# myStravaB_V2.net
KiCad netlist of a schematic drawn in EAGLE
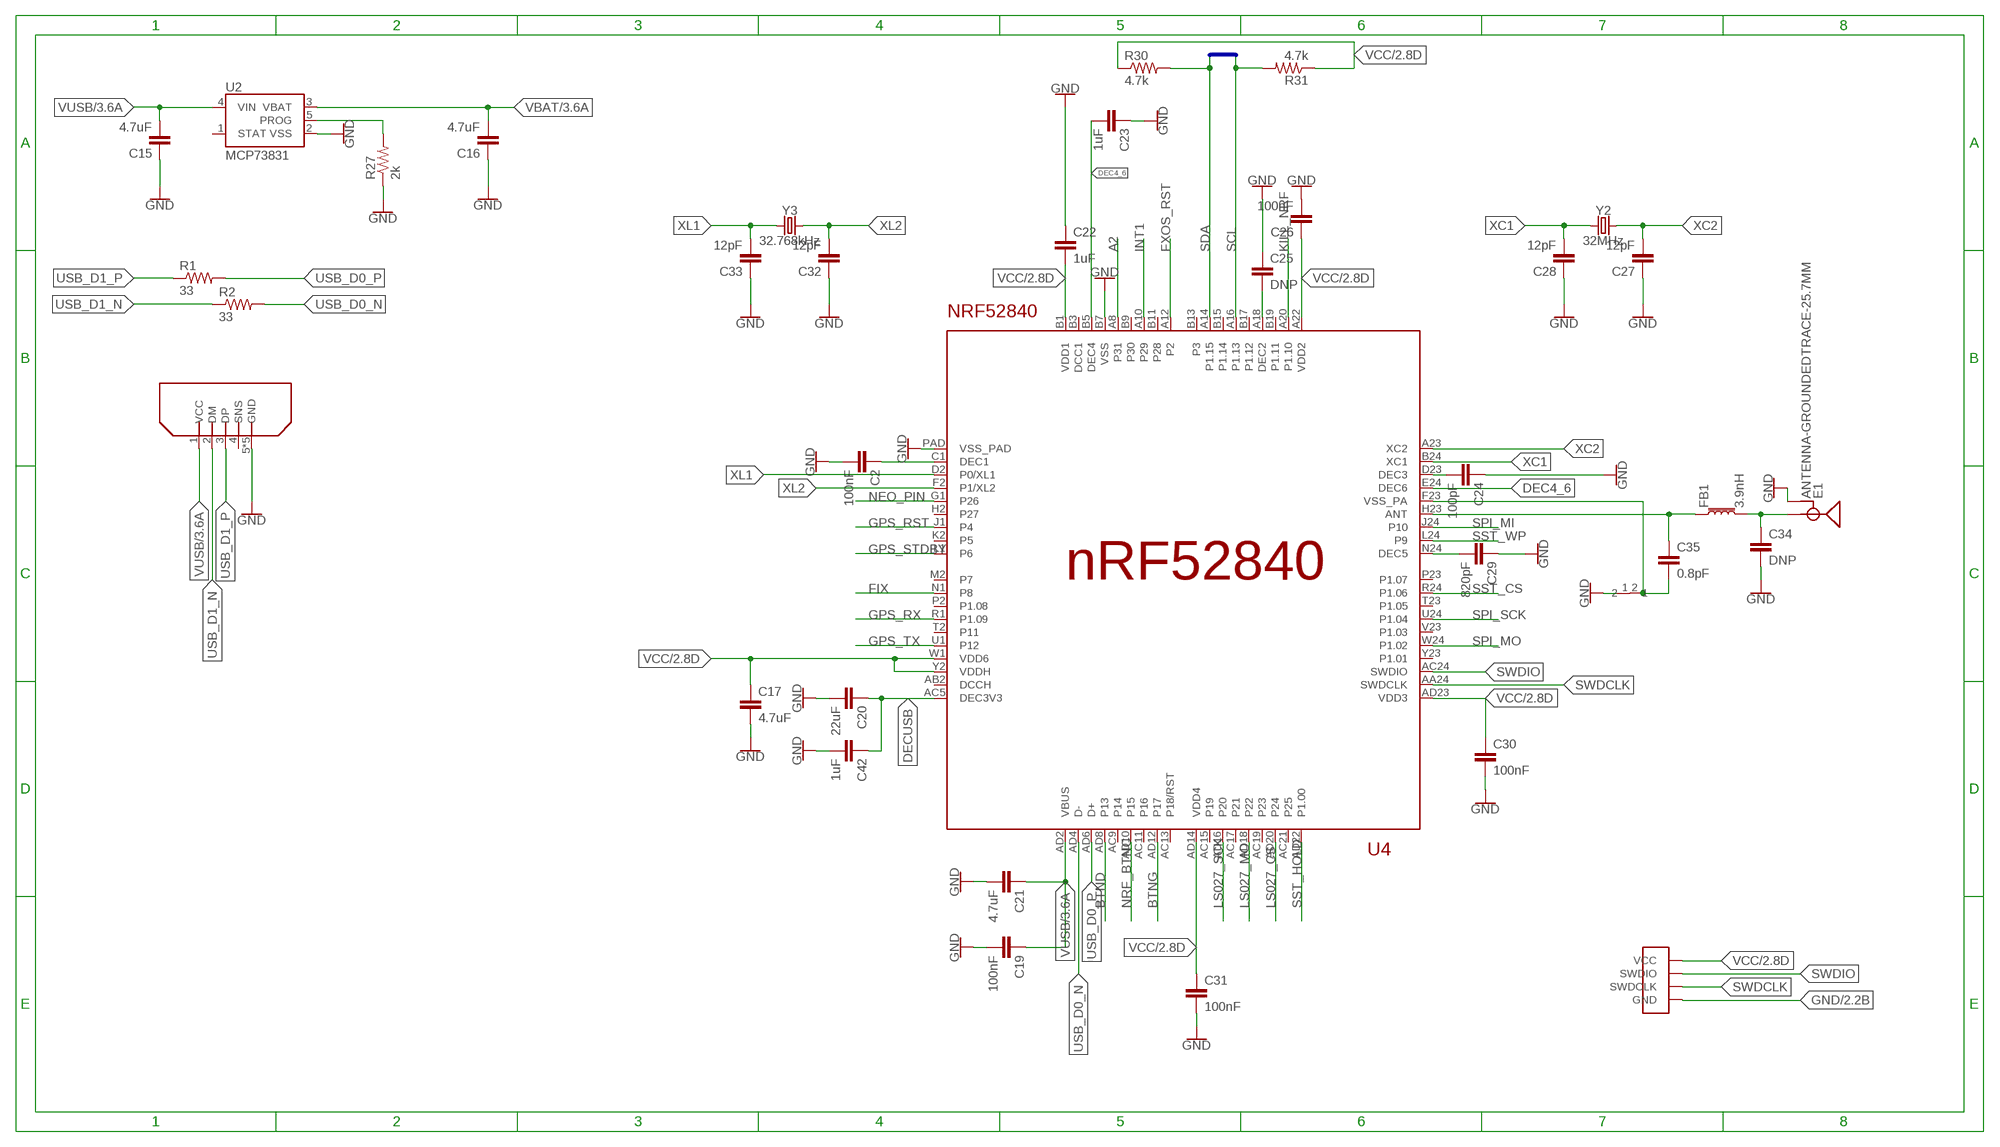
[diagram p0: schematic, sheet 1]
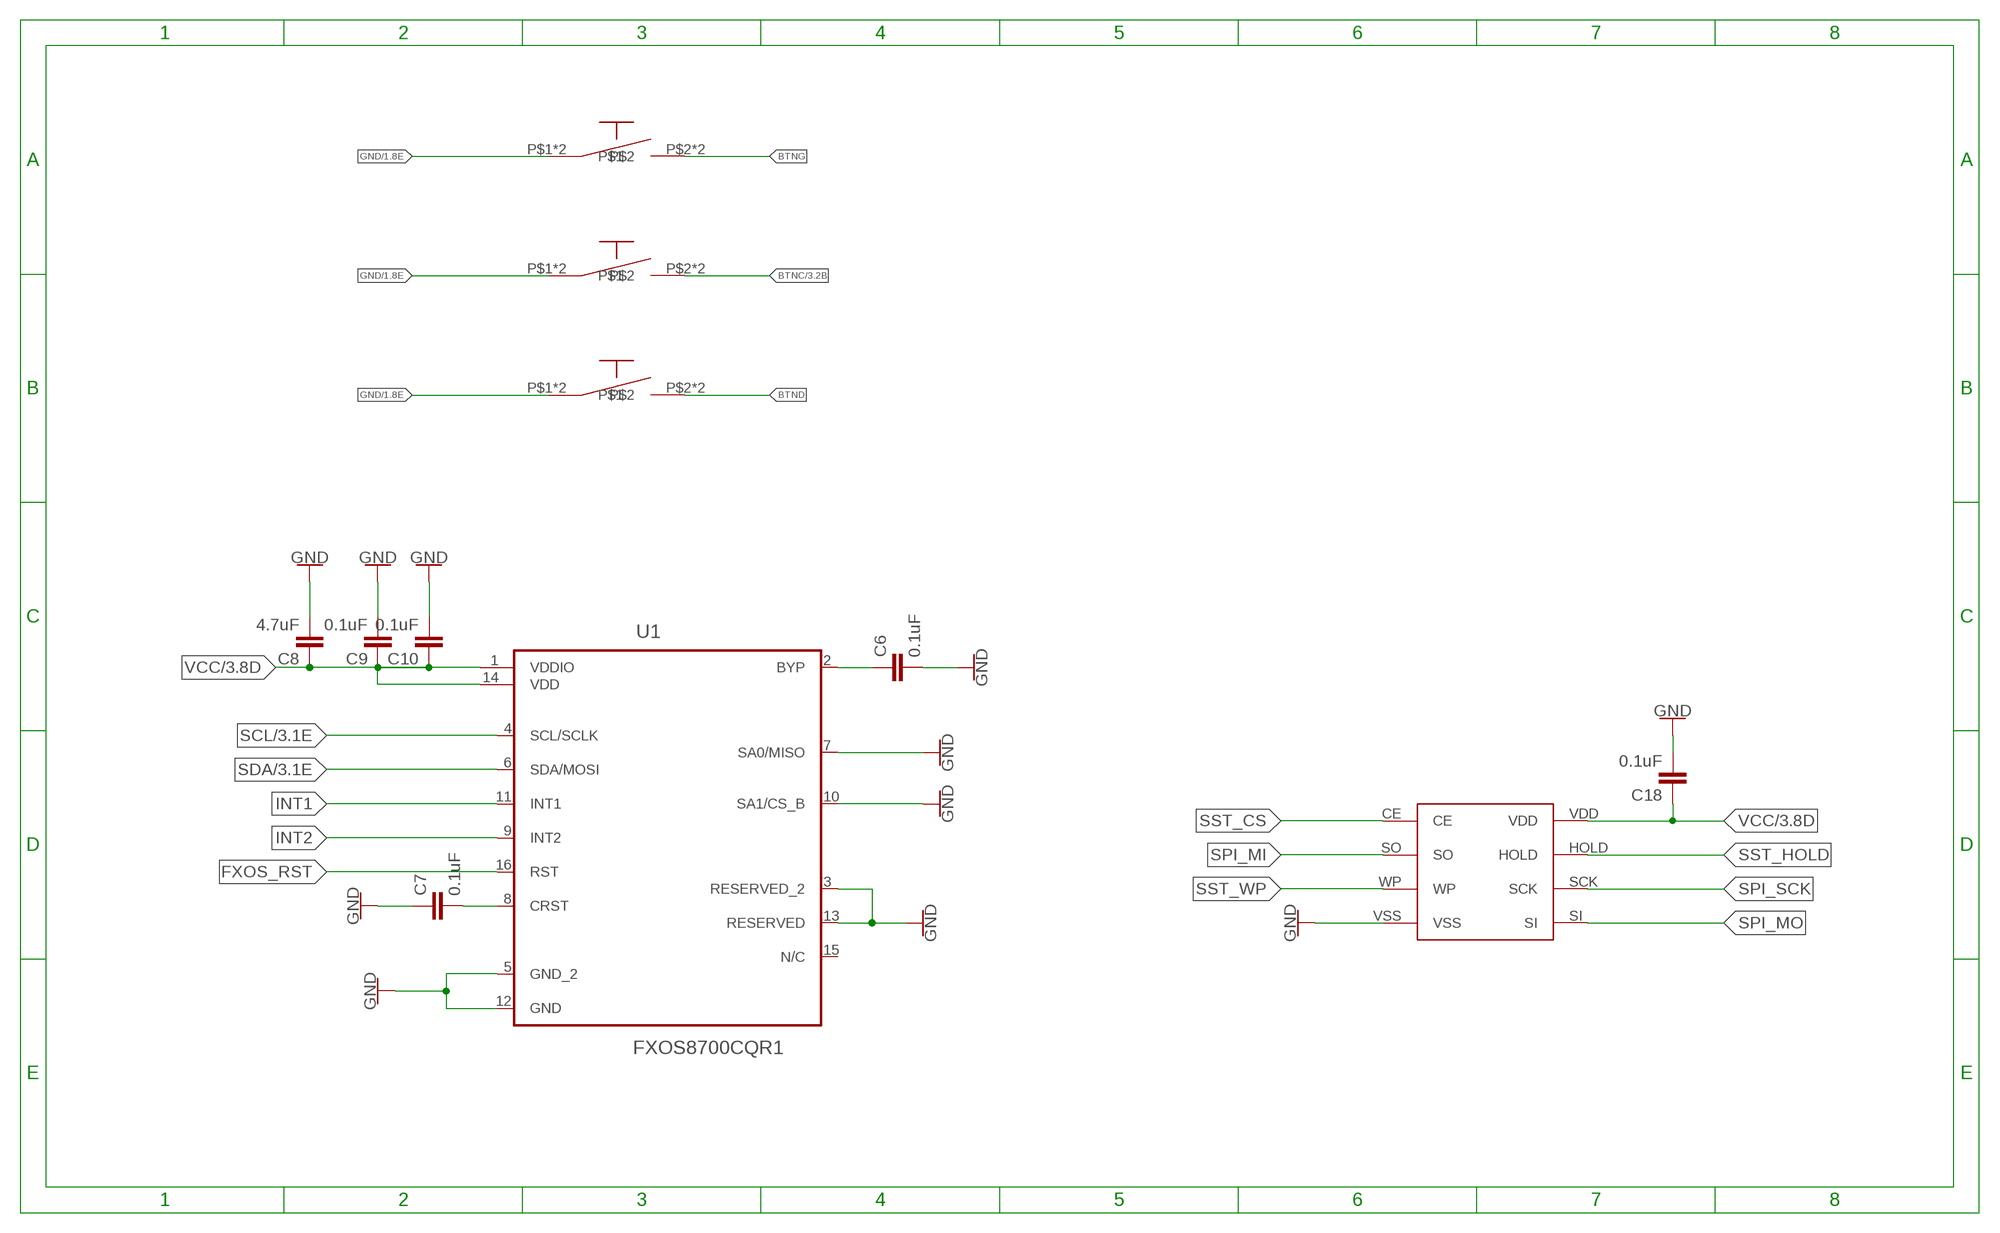
[diagram p1: schematic, sheet 2]
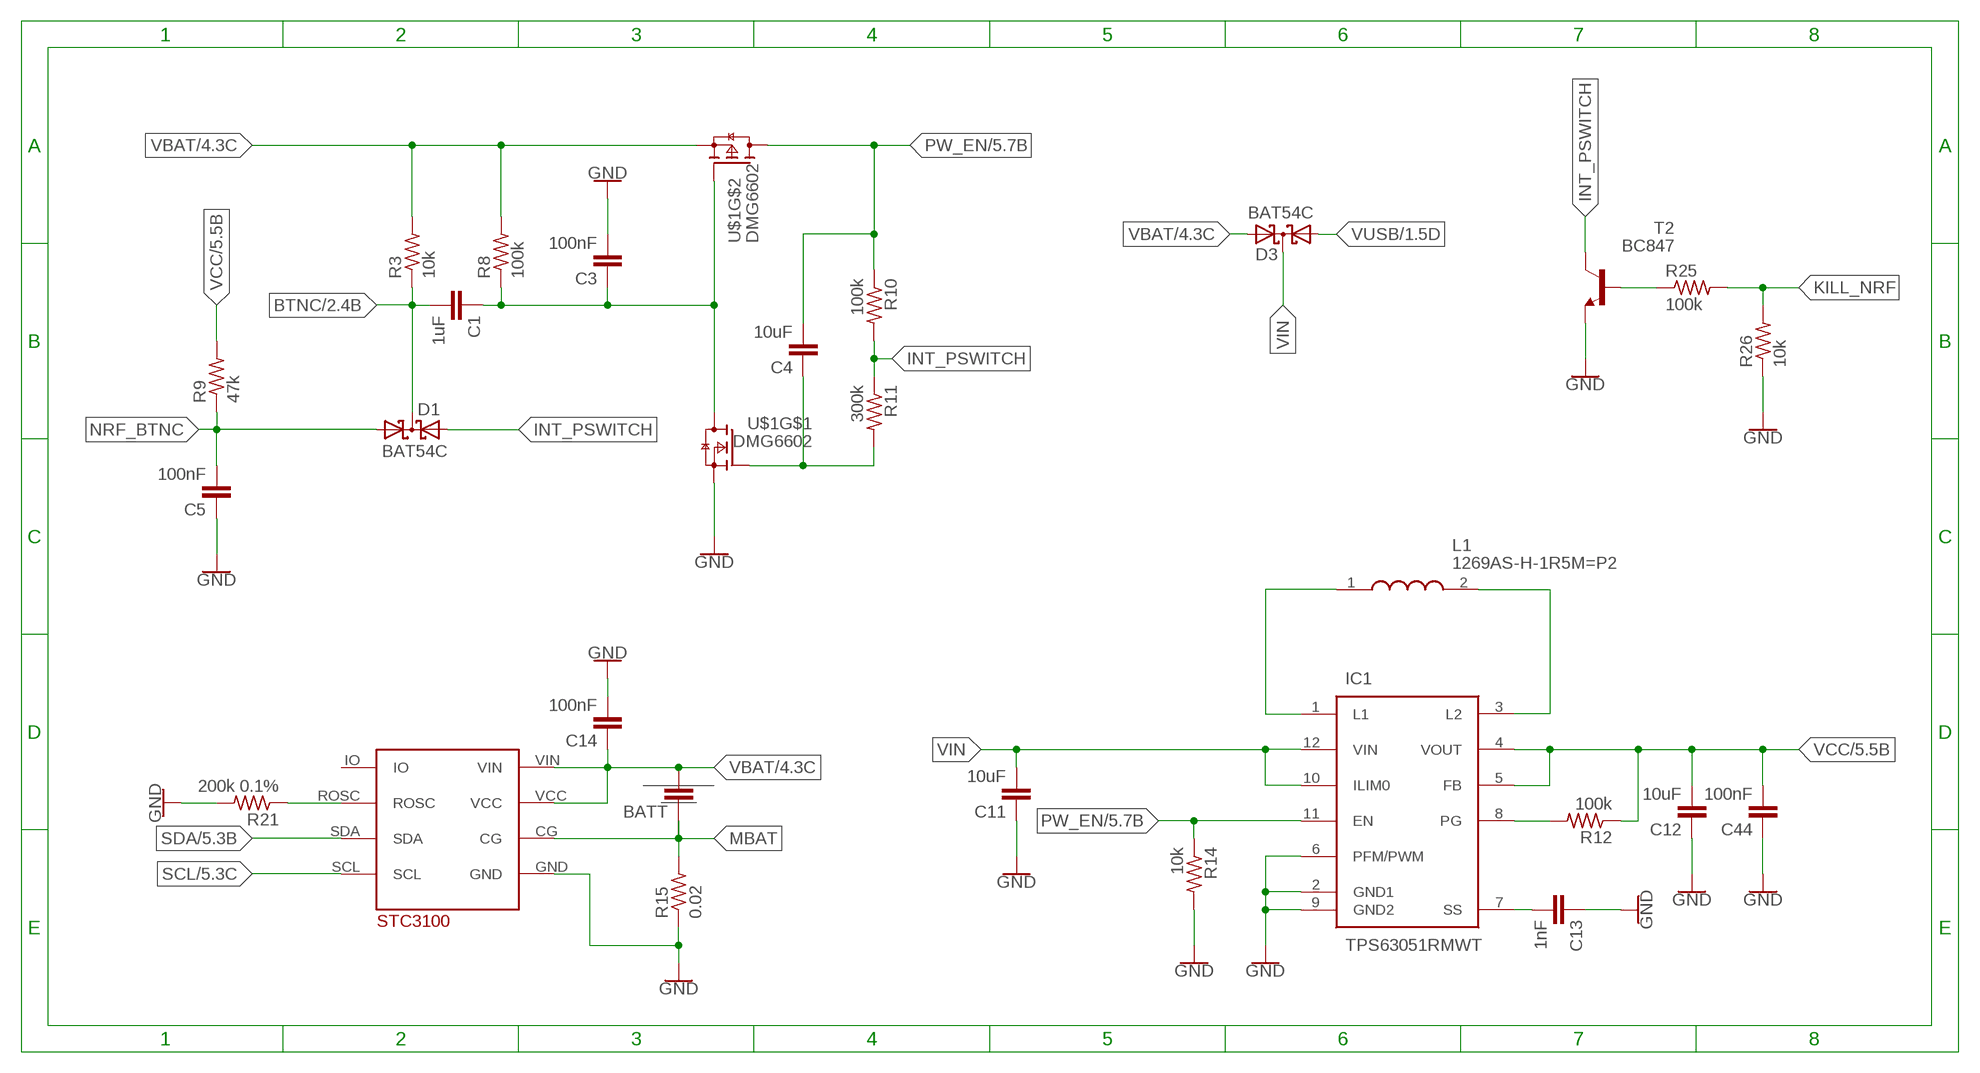
[diagram p2: schematic, sheet 3]
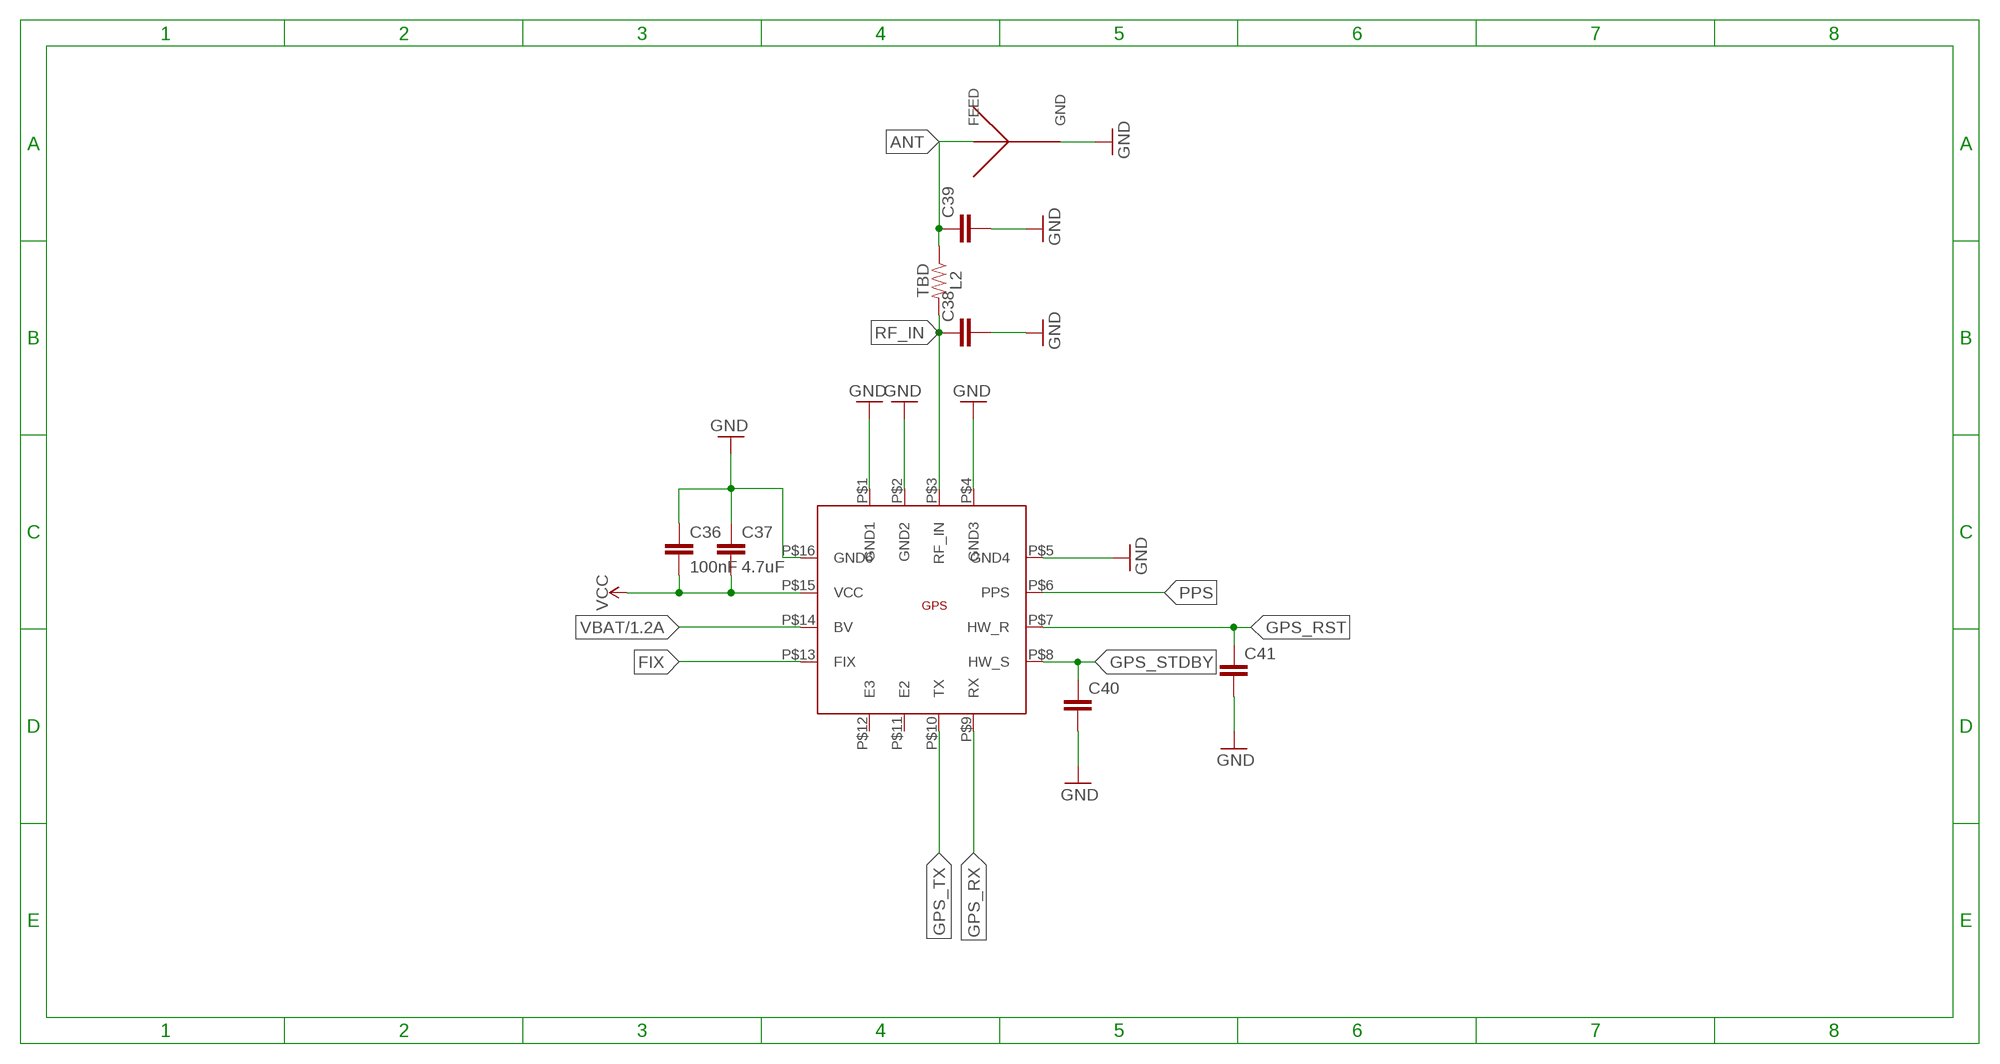
[diagram p3: schematic, sheet 4]
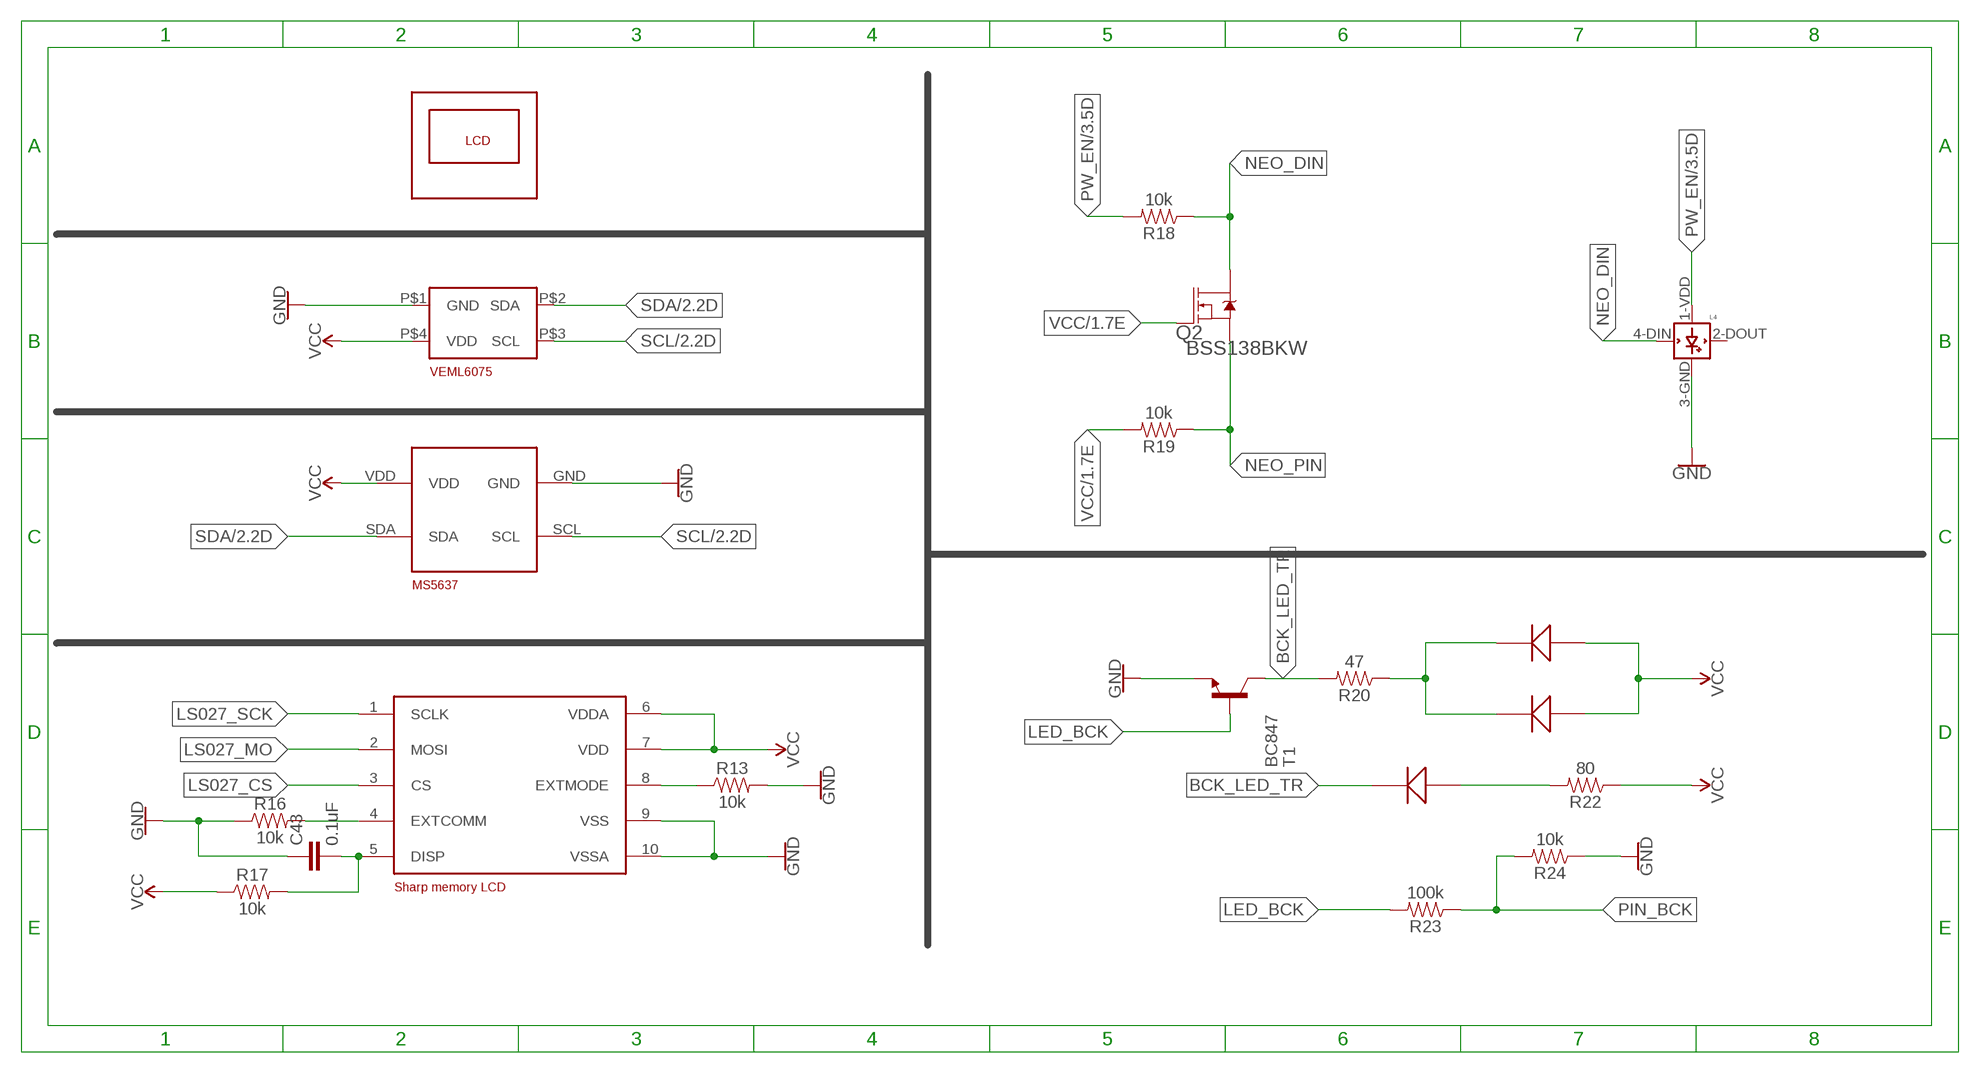
[diagram p4: schematic, sheet 5]

(export (version "E")
  (design (tool "Eeschema 10.0.6"))
  (components
    (comp (ref "C43")
      (value "0.1uF")
      (footprint "eagle-import:0603")
      (libsource (lib "eagle-import") (part "0.1UF-0603-25V-(+80/-20%)"))
    )
    (comp (ref "L4")
      (value "WS2812B")
      (footprint "eagle-import:WS2812B")
      (libsource (lib "eagle-import") (part "WS2812B"))
    )
    (comp (ref "MS1")
      (value "MS5637")
      (footprint "eagle-import:MS5637")
      (libsource (lib "eagle-import") (part "MS5637"))
    )
    (comp (ref "Q2")
      (value "BSS138BKW")
      (footprint "eagle-import:SOT65P210X110-3N")
      (libsource (lib "eagle-import") (part "BSS138BKW"))
    )
    (comp (ref "R13")
      (value "10k")
      (footprint "eagle-import:0603")
      (libsource (lib "eagle-import") (part "4.7KOHM-0603-1/10W-1%"))
    )
    (comp (ref "R16")
      (value "10k")
      (footprint "eagle-import:0603")
      (libsource (lib "eagle-import") (part "4.7KOHM-0603-1/10W-1%"))
    )
    (comp (ref "R17")
      (value "10k")
      (footprint "eagle-import:0603")
      (libsource (lib "eagle-import") (part "4.7KOHM-0603-1/10W-1%"))
    )
    (comp (ref "R18")
      (value "10k")
      (footprint "eagle-import:0603")
      (libsource (lib "eagle-import") (part "4.7KOHM-0603-1/10W-1%"))
    )
    (comp (ref "R19")
      (value "10k")
      (footprint "eagle-import:0603")
      (libsource (lib "eagle-import") (part "4.7KOHM-0603-1/10W-1%"))
    )
    (comp (ref "R20")
      (value "47")
      (footprint "eagle-import:0603")
      (libsource (lib "eagle-import") (part "4.7KOHM-0603-1/10W-1%"))
    )
    (comp (ref "R22")
      (value "80")
      (footprint "eagle-import:0603")
      (libsource (lib "eagle-import") (part "4.7KOHM-0603-1/10W-1%"))
    )
    (comp (ref "R23")
      (value "100k")
      (footprint "eagle-import:0603")
      (libsource (lib "eagle-import") (part "4.7KOHM-0603-1/10W-1%"))
    )
    (comp (ref "R24")
      (value "10k")
      (footprint "eagle-import:0603")
      (libsource (lib "eagle-import") (part "4.7KOHM-0603-1/10W-1%"))
    )
    (comp (ref "T1")
      (value "BC847")
      (footprint "eagle-import:SOT23")
      (libsource (lib "eagle-import") (part "BC847"))
    )
    (comp (ref "U$14")
      (value "VEML6075")
      (footprint "eagle-import:VEML6075")
      (libsource (lib "eagle-import") (part "VEML6075"))
    )
    (comp (ref "U$15")
      (value "SHARP27_FOOTPRINT")
      (footprint "eagle-import:LCD27")
      (libsource (lib "eagle-import") (part "SHARP27_FOOTPRINT"))
    )
    (comp (ref "U$16")
      (value "SHARP27")
      (footprint "eagle-import:SHARP27")
      (libsource (lib "eagle-import") (part "SHARP27"))
    )
    (comp (ref "U$17")
      (value "KPA-2106SECK")
      (footprint "eagle-import:KPA-2106SECK")
      (libsource (lib "eagle-import") (part "KPA-2106SECK"))
    )
    (comp (ref "U$18")
      (value "KPA-2106SECK")
      (footprint "eagle-import:KPA-2106SECK")
      (libsource (lib "eagle-import") (part "KPA-2106SECK"))
    )
    (comp (ref "U$19")
      (value "KPA-2106SECK")
      (footprint "eagle-import:KPA-2106SECK")
      (libsource (lib "eagle-import") (part "KPA-2106SECK"))
    )
    (comp (ref "C36")
      (value "100nF")
      (footprint "eagle-import:C0603")
      (libsource (lib "eagle-import") (part "rcl_334_C-EUC0603"))
    )
    (comp (ref "C37")
      (value "4.7uF")
      (footprint "eagle-import:C0603")
      (libsource (lib "eagle-import") (part "rcl_334_C-EUC0603"))
    )
    (comp (ref "C38")
      (value "C-EUC0603")
      (footprint "eagle-import:C0603")
      (libsource (lib "eagle-import") (part "rcl_334_C-EUC0603"))
    )
    (comp (ref "C39")
      (value "C-EUC0603")
      (footprint "eagle-import:C0603")
      (libsource (lib "eagle-import") (part "rcl_334_C-EUC0603"))
    )
    (comp (ref "C40")
      (value "C-EUC0603")
      (footprint "eagle-import:C0603")
      (libsource (lib "eagle-import") (part "rcl_334_C-EUC0603"))
    )
    (comp (ref "C41")
      (value "C-EUC0603")
      (footprint "eagle-import:C0603")
      (libsource (lib "eagle-import") (part "rcl_334_C-EUC0603"))
    )
    (comp (ref "L2")
      (value "TBD")
      (footprint "eagle-import:0603")
      (libsource (lib "eagle-import") (part "4.7KOHM-0603-1/10W-1%"))
    )
    (comp (ref "U$4")
      (value "SR4G008")
      (footprint "eagle-import:SR4G008")
      (libsource (lib "eagle-import") (part "SR4G008"))
    )
    (comp (ref "U$5")
      (value "M10578")
      (footprint "eagle-import:M10578")
      (libsource (lib "eagle-import") (part "M10578"))
    )
    (comp (ref "C2")
      (value "100nF")
      (footprint "eagle-import:C0603")
      (libsource (lib "eagle-import") (part "C-EUC0603"))
    )
    (comp (ref "C15")
      (value "4.7uF")
      (footprint "eagle-import:C0805")
      (libsource (lib "eagle-import") (part "C-EUC0805"))
    )
    (comp (ref "C16")
      (value "4.7uF")
      (footprint "eagle-import:C0805")
      (libsource (lib "eagle-import") (part "C-EUC0805"))
    )
    (comp (ref "C17")
      (value "4.7uF")
      (footprint "eagle-import:C0603")
      (libsource (lib "eagle-import") (part "rcl_334_C-EUC0603"))
    )
    (comp (ref "C19")
      (value "100nF")
      (footprint "eagle-import:C0603")
      (libsource (lib "eagle-import") (part "rcl_334_C-EUC0603"))
    )
    (comp (ref "C20")
      (value "22uF")
      (footprint "eagle-import:C0603")
      (libsource (lib "eagle-import") (part "rcl_334_C-EUC0603"))
    )
    (comp (ref "C21")
      (value "4.7uF")
      (footprint "eagle-import:C0805")
      (libsource (lib "eagle-import") (part "rcl_334_C-EUC0805"))
    )
    (comp (ref "C22")
      (value "1uF")
      (footprint "eagle-import:0603")
      (libsource (lib "eagle-import") (part "4.7UF0603"))
    )
    (comp (ref "C23")
      (value "1uF")
      (footprint "eagle-import:0603")
      (libsource (lib "eagle-import") (part "4.7UF0603"))
    )
    (comp (ref "C24")
      (value "100pF")
      (footprint "eagle-import:C0603")
      (libsource (lib "eagle-import") (part "C-EUC0603"))
    )
    (comp (ref "C25")
      (value "DNP")
      (footprint "eagle-import:C0402")
      (libsource (lib "eagle-import") (part "C-EUC0402"))
    )
    (comp (ref "C26")
      (value "100nF")
      (footprint "eagle-import:C0603")
      (libsource (lib "eagle-import") (part "C-EUC0603"))
    )
    (comp (ref "C27")
      (value "12pF")
      (footprint "eagle-import:C0402")
      (libsource (lib "eagle-import") (part "C-EUC0402"))
    )
    (comp (ref "C28")
      (value "12pF")
      (footprint "eagle-import:C0402")
      (libsource (lib "eagle-import") (part "C-EUC0402"))
    )
    (comp (ref "C29")
      (value "820pF")
      (footprint "eagle-import:C0603")
      (libsource (lib "eagle-import") (part "C-EUC0603"))
    )
    (comp (ref "C30")
      (value "100nF")
      (footprint "eagle-import:C0402")
      (libsource (lib "eagle-import") (part "C-EUC0402"))
    )
    (comp (ref "C31")
      (value "100nF")
      (footprint "eagle-import:C0402")
      (libsource (lib "eagle-import") (part "C-EUC0402"))
    )
    (comp (ref "C32")
      (value "12pF")
      (footprint "eagle-import:C0603")
      (libsource (lib "eagle-import") (part "C-EUC0603"))
    )
    (comp (ref "C33")
      (value "12pF")
      (footprint "eagle-import:C0603")
      (libsource (lib "eagle-import") (part "C-EUC0603"))
    )
    (comp (ref "C34")
      (value "DNP")
      (footprint "eagle-import:0603")
      (libsource (lib "eagle-import") (part "4.7UF0603"))
    )
    (comp (ref "C35")
      (value "0.8pF")
      (footprint "eagle-import:C0402")
      (libsource (lib "eagle-import") (part "C-EUC0402"))
    )
    (comp (ref "C42")
      (value "1uF")
      (footprint "eagle-import:C0603")
      (libsource (lib "eagle-import") (part "rcl_334_C-EUC0603"))
    )
    (comp (ref "E1")
      (value "ANTENNA-GROUNDEDTRACE-25.7MM")
      (footprint "eagle-import:TRACE_ANTENNA_2.4GHZ_25.7MM")
      (libsource (lib "eagle-import") (part "ANTENNA-GROUNDEDTRACE-25.7MM"))
    )
    (comp (ref "FB1")
      (value "3.9nH")
      (footprint "eagle-import:0603")
      (libsource (lib "eagle-import") (part "FERRITE_BEAD-0603"))
    )
    (comp (ref "R1")
      (value "33")
      (footprint "eagle-import:R0603")
      (libsource (lib "eagle-import") (part "R-US_R0603"))
    )
    (comp (ref "R2")
      (value "33")
      (footprint "eagle-import:R0603")
      (libsource (lib "eagle-import") (part "R-US_R0603"))
    )
    (comp (ref "R27")
      (value "2k")
      (footprint "eagle-import:R0603")
      (libsource (lib "eagle-import") (part "R-US_R0603"))
    )
    (comp (ref "R30")
      (value "4.7k")
      (footprint "eagle-import:R0603")
      (libsource (lib "eagle-import") (part "R-US_R0603"))
    )
    (comp (ref "R31")
      (value "4.7k")
      (footprint "eagle-import:R0603")
      (libsource (lib "eagle-import") (part "R-US_R0603"))
    )
    (comp (ref "U$3")
      (value "ZX80B5P")
      (footprint "eagle-import:ZX80B5P")
      (libsource (lib "eagle-import") (part "ZX80B5P"))
    )
    (comp (ref "U$7")
      (value "PROG_SMD")
      (footprint "eagle-import:PROG_SMD")
      (libsource (lib "eagle-import") (part "PROG_SMD"))
    )
    (comp (ref "U$8")
      (value "NET_CONN")
      (footprint "eagle-import:NET_CONN")
      (libsource (lib "eagle-import") (part "NET_CONN"))
    )
    (comp (ref "U2")
      (value "MCP73831")
      (footprint "eagle-import:SOT23-5")
      (libsource (lib "eagle-import") (part "MCP73831"))
    )
    (comp (ref "U4")
      (value "NRF52840")
      (footprint "eagle-import:AQFN73")
      (fields (field (name "SPICEPREFIX") "X"))
      (libsource (lib "eagle-import") (part "NRF52840"))
    )
    (comp (ref "Y2")
      (value "32MHz")
      (footprint "eagle-import:CRYSTAL-SMD-5X3.2-4PAD")
      (libsource (lib "eagle-import") (part "CRYSTAL-16MHZSMD-5X3.2"))
    )
    (comp (ref "Y3")
      (value "32.768kHz")
      (footprint "eagle-import:CRYSTAL-SMD-3.2X1.5MM")
      (libsource (lib "eagle-import") (part "CRYSTAL-32.768KHZSMD-3.2X1.5"))
    )
    (comp (ref "BATT")
      (value "C-EUC1210")
      (footprint "eagle-import:C1210")
      (libsource (lib "eagle-import") (part "rcl_334_C-EUC1210"))
    )
    (comp (ref "C1")
      (value "1uF")
      (footprint "eagle-import:0603")
      (libsource (lib "eagle-import") (part "4.7UF0603"))
    )
    (comp (ref "C3")
      (value "100nF")
      (footprint "eagle-import:0603")
      (libsource (lib "eagle-import") (part "4.7UF0603"))
    )
    (comp (ref "C4")
      (value "10uF")
      (footprint "eagle-import:0603")
      (libsource (lib "eagle-import") (part "4.7UF0603"))
    )
    (comp (ref "C5")
      (value "100nF")
      (footprint "eagle-import:0603")
      (libsource (lib "eagle-import") (part "4.7UF0603"))
    )
    (comp (ref "C11")
      (value "10uF")
      (footprint "eagle-import:C0805")
      (libsource (lib "eagle-import") (part "rcl_334_C-EUC0805"))
    )
    (comp (ref "C12")
      (value "10uF")
      (footprint "eagle-import:C0603")
      (libsource (lib "eagle-import") (part "rcl_334_C-EUC0603"))
    )
    (comp (ref "C13")
      (value "1nF")
      (footprint "eagle-import:C0603")
      (libsource (lib "eagle-import") (part "rcl_334_C-EUC0603"))
    )
    (comp (ref "C14")
      (value "100nF")
      (footprint "eagle-import:C0603")
      (libsource (lib "eagle-import") (part "rcl_334_C-EUC0603"))
    )
    (comp (ref "C44")
      (value "100nF")
      (footprint "eagle-import:C0603")
      (libsource (lib "eagle-import") (part "rcl_334_C-EUC0603"))
    )
    (comp (ref "D1")
      (value "BAT54C")
      (footprint "eagle-import:SOT23")
      (libsource (lib "eagle-import") (part "BAT54C"))
    )
    (comp (ref "D3")
      (value "BAT54C")
      (footprint "eagle-import:SOT23")
      (libsource (lib "eagle-import") (part "BAT54C"))
    )
    (comp (ref "IC1")
      (value "TPS63051RMWT")
      (footprint "eagle-import:QFN50P250X250X100-12N")
      (fields (field (name "RS_PART_NUMBER") "1330763"))
      (libsource (lib "eagle-import") (part "TPS63051RMWT"))
    )
    (comp (ref "L1")
      (value "1269AS-H-1R5M=P2")
      (footprint "eagle-import:INDC2520X110N")
      (libsource (lib "eagle-import") (part "1269AS-H-1R5M=P2"))
    )
    (comp (ref "R3")
      (value "10k")
      (footprint "eagle-import:R0603")
      (libsource (lib "eagle-import") (part "R-US_R0603"))
    )
    (comp (ref "R8")
      (value "100k")
      (footprint "eagle-import:R0603")
      (libsource (lib "eagle-import") (part "R-US_R0603"))
    )
    (comp (ref "R9")
      (value "47k")
      (footprint "eagle-import:R0603")
      (libsource (lib "eagle-import") (part "R-US_R0603"))
    )
    (comp (ref "R10")
      (value "100k")
      (footprint "eagle-import:R0603")
      (libsource (lib "eagle-import") (part "R-US_R0603"))
    )
    (comp (ref "R11")
      (value "300k")
      (footprint "eagle-import:R0603")
      (libsource (lib "eagle-import") (part "R-US_R0603"))
    )
    (comp (ref "R12")
      (value "100k")
      (footprint "eagle-import:R0603")
      (libsource (lib "eagle-import") (part "R-US_R0603"))
    )
    (comp (ref "R14")
      (value "10k")
      (footprint "eagle-import:R0603")
      (libsource (lib "eagle-import") (part "R-US_R0603"))
    )
    (comp (ref "R15")
      (value "0.02")
      (footprint "eagle-import:R0603")
      (libsource (lib "eagle-import") (part "R-US_R0603"))
    )
    (comp (ref "R21")
      (value "200k 0.1%")
      (footprint "eagle-import:R0603")
      (libsource (lib "eagle-import") (part "R-US_R0603"))
    )
    (comp (ref "R25")
      (value "100k")
      (footprint "eagle-import:R0603")
      (libsource (lib "eagle-import") (part "R-US_R0603"))
    )
    (comp (ref "R26")
      (value "10k")
      (footprint "eagle-import:R0603")
      (libsource (lib "eagle-import") (part "R-US_R0603"))
    )
    (comp (ref "T2")
      (value "BC847")
      (footprint "eagle-import:SOT23")
      (libsource (lib "eagle-import") (part "BC847"))
    )
    (comp (ref "U$1")
      (value "DMG6602")
      (footprint "eagle-import:TSOT26")
      (fields (field (name "MPN") "DMG6602SVTQ"))
      (libsource (lib "eagle-import") (part "DMG6602"))
    )
    (comp (ref "U$6")
      (value "STC3100")
      (footprint "eagle-import:STC3100")
      (libsource (lib "eagle-import") (part "STC3100"))
    )
    (comp (ref "BTNC1")
      (value "SKRMAAE010")
      (footprint "eagle-import:SKRMAAE010")
      (libsource (lib "eagle-import") (part "SKRMAAE010"))
    )
    (comp (ref "BTND1")
      (value "SKRMAAE010")
      (footprint "eagle-import:SKRMAAE010")
      (libsource (lib "eagle-import") (part "SKRMAAE010"))
    )
    (comp (ref "BTNG1")
      (value "SKRMAAE010")
      (footprint "eagle-import:SKRMAAE010")
      (libsource (lib "eagle-import") (part "SKRMAAE010"))
    )
    (comp (ref "C6")
      (value "0.1uF")
      (footprint "eagle-import:0603")
      (libsource (lib "eagle-import") (part "4.7UF0603"))
    )
    (comp (ref "C7")
      (value "0.1uF")
      (footprint "eagle-import:0603")
      (libsource (lib "eagle-import") (part "4.7UF0603"))
    )
    (comp (ref "C8")
      (value "4.7uF")
      (footprint "eagle-import:0603")
      (libsource (lib "eagle-import") (part "4.7UF0603"))
    )
    (comp (ref "C9")
      (value "0.1uF")
      (footprint "eagle-import:0603")
      (libsource (lib "eagle-import") (part "4.7UF0603"))
    )
    (comp (ref "C10")
      (value "0.1uF")
      (footprint "eagle-import:0603")
      (libsource (lib "eagle-import") (part "4.7UF0603"))
    )
    (comp (ref "C18")
      (value "0.1uF")
      (footprint "eagle-import:0603")
      (libsource (lib "eagle-import") (part "4.7UF0603"))
    )
    (comp (ref "U$2")
      (value "FLASH")
      (footprint "eagle-import:SOIC8")
      (libsource (lib "eagle-import") (part "FLASH"))
    )
    (comp (ref "U1")
      (value "FXOS8700CQR1")
      (footprint "eagle-import:QFN50P300X300X120-16N")
      (libsource (lib "eagle-import") (part "FXOS8700CQR1"))
    )
  )
  (nets
    (net (code "1") (name "A2") (class "Default")
      (node (ref "U4") (pin "A8") (pinfunction "P31_A8") (pintype "bidirectional"))
    )
    (net (code "2") (name "ANT") (class "Default")
      (node (ref "C39") (pin "1") (pinfunction "1_1") (pintype "passive"))
      (node (ref "L2") (pin "1") (pinfunction "1_1") (pintype "passive"))
      (node (ref "U$4") (pin "P$2") (pinfunction "FEED_P$2") (pintype "bidirectional"))
    )
    (net (code "3") (name "BCK_LED_TR") (class "Default")
      (node (ref "R20") (pin "2") (pinfunction "2_2") (pintype "passive"))
      (node (ref "T1") (pin "3") (pinfunction "C_3") (pintype "passive"))
      (node (ref "U$19") (pin "P$1") (pinfunction "P$1_P$1") (pintype "bidirectional"))
    )
    (net (code "4") (name "BTNC") (class "Default")
      (node (ref "BTNC1") (pin "P$2") (pinfunction "P$2_P$2") (pintype "bidirectional"))
      (node (ref "BTNC1") (pin "P$4") (pinfunction "P$2_P$4") (pintype "bidirectional"))
      (node (ref "C1") (pin "2") (pinfunction "2_2") (pintype "passive"))
      (node (ref "D1") (pin "3") (pinfunction "CC_3") (pintype "passive"))
      (node (ref "R3") (pin "1") (pinfunction "1_1") (pintype "passive"))
    )
    (net (code "5") (name "BTND") (class "Default")
      (node (ref "BTND1") (pin "P$2") (pinfunction "P$2_P$2") (pintype "bidirectional"))
      (node (ref "BTND1") (pin "P$4") (pinfunction "P$2_P$4") (pintype "bidirectional"))
      (node (ref "U4") (pin "AD8") (pinfunction "P13_AD8") (pintype "bidirectional"))
    )
    (net (code "6") (name "BTNG") (class "Default")
      (node (ref "BTNG1") (pin "P$2") (pinfunction "P$2_P$2") (pintype "bidirectional"))
      (node (ref "BTNG1") (pin "P$4") (pinfunction "P$2_P$4") (pintype "bidirectional"))
      (node (ref "U4") (pin "AD12") (pinfunction "P17_AD12") (pintype "bidirectional"))
    )
    (net (code "7") (name "DEC4_6") (class "Default")
      (node (ref "C23") (pin "2") (pinfunction "2_2") (pintype "passive"))
      (node (ref "U4") (pin "B5") (pinfunction "DEC4_B5") (pintype "bidirectional"))
      (node (ref "U4") (pin "E24") (pinfunction "DEC6_E24") (pintype "bidirectional"))
    )
    (net (code "8") (name "DECUSB") (class "Default")
      (node (ref "C20") (pin "1") (pinfunction "1_1") (pintype "passive"))
      (node (ref "C42") (pin "1") (pinfunction "1_1") (pintype "passive"))
      (node (ref "U4") (pin "AC5") (pinfunction "DEC3V3_AC5") (pintype "bidirectional"))
    )
    (net (code "9") (name "FIX") (class "Default")
      (node (ref "U$5") (pin "P$13") (pinfunction "FIX_P$13") (pintype "bidirectional"))
      (node (ref "U4") (pin "N1") (pinfunction "P8_N1") (pintype "bidirectional"))
    )
    (net (code "10") (name "FXOS_RST") (class "Default")
      (node (ref "U1") (pin "16") (pinfunction "RST_16") (pintype "input"))
      (node (ref "U4") (pin "A12") (pinfunction "P2_A12") (pintype "bidirectional"))
    )
    (net (code "11") (name "GND") (class "Default")
      (node (ref "BTNC1") (pin "P$1") (pinfunction "P$1_P$1") (pintype "bidirectional"))
      (node (ref "BTNC1") (pin "P$3") (pinfunction "P$1_P$3") (pintype "bidirectional"))
      (node (ref "BTND1") (pin "P$1") (pinfunction "P$1_P$1") (pintype "bidirectional"))
      (node (ref "BTND1") (pin "P$3") (pinfunction "P$1_P$3") (pintype "bidirectional"))
      (node (ref "BTNG1") (pin "P$1") (pinfunction "P$1_P$1") (pintype "bidirectional"))
      (node (ref "BTNG1") (pin "P$3") (pinfunction "P$1_P$3") (pintype "bidirectional"))
      (node (ref "C10") (pin "2") (pinfunction "2_2") (pintype "passive"))
      (node (ref "C11") (pin "1") (pinfunction "1_1") (pintype "passive"))
      (node (ref "C12") (pin "1") (pinfunction "1_1") (pintype "passive"))
      (node (ref "C13") (pin "1") (pinfunction "1_1") (pintype "passive"))
      (node (ref "C14") (pin "2") (pinfunction "2_2") (pintype "passive"))
      (node (ref "C15") (pin "1") (pinfunction "1_1") (pintype "passive"))
      (node (ref "C16") (pin "1") (pinfunction "1_1") (pintype "passive"))
      (node (ref "C17") (pin "2") (pinfunction "2_2") (pintype "passive"))
      (node (ref "C18") (pin "2") (pinfunction "2_2") (pintype "passive"))
      (node (ref "C19") (pin "2") (pinfunction "2_2") (pintype "passive"))
      (node (ref "C2") (pin "2") (pinfunction "2_2") (pintype "passive"))
      (node (ref "C20") (pin "2") (pinfunction "2_2") (pintype "passive"))
      (node (ref "C21") (pin "2") (pinfunction "2_2") (pintype "passive"))
      (node (ref "C22") (pin "1") (pinfunction "1_1") (pintype "passive"))
      (node (ref "C23") (pin "1") (pinfunction "1_1") (pintype "passive"))
      (node (ref "C24") (pin "1") (pinfunction "1_1") (pintype "passive"))
      (node (ref "C25") (pin "1") (pinfunction "1_1") (pintype "passive"))
      (node (ref "C26") (pin "2") (pinfunction "2_2") (pintype "passive"))
      (node (ref "C27") (pin "1") (pinfunction "1_1") (pintype "passive"))
      (node (ref "C28") (pin "1") (pinfunction "1_1") (pintype "passive"))
      (node (ref "C29") (pin "1") (pinfunction "1_1") (pintype "passive"))
      (node (ref "C3") (pin "2") (pinfunction "2_2") (pintype "passive"))
      (node (ref "C30") (pin "2") (pinfunction "2_2") (pintype "passive"))
      (node (ref "C31") (pin "2") (pinfunction "2_2") (pintype "passive"))
      (node (ref "C32") (pin "1") (pinfunction "1_1") (pintype "passive"))
      (node (ref "C33") (pin "1") (pinfunction "1_1") (pintype "passive"))
      (node (ref "C34") (pin "2") (pinfunction "2_2") (pintype "passive"))
      (node (ref "C36") (pin "1") (pinfunction "1_1") (pintype "passive"))
      (node (ref "C37") (pin "1") (pinfunction "1_1") (pintype "passive"))
      (node (ref "C38") (pin "2") (pinfunction "2_2") (pintype "passive"))
      (node (ref "C39") (pin "2") (pinfunction "2_2") (pintype "passive"))
      (node (ref "C40") (pin "2") (pinfunction "2_2") (pintype "passive"))
      (node (ref "C41") (pin "2") (pinfunction "2_2") (pintype "passive"))
      (node (ref "C42") (pin "2") (pinfunction "2_2") (pintype "passive"))
      (node (ref "C43") (pin "1") (pinfunction "1_1") (pintype "passive"))
      (node (ref "C44") (pin "1") (pinfunction "1_1") (pintype "passive"))
      (node (ref "C5") (pin "1") (pinfunction "1_1") (pintype "passive"))
      (node (ref "C6") (pin "2") (pinfunction "2_2") (pintype "passive"))
      (node (ref "C7") (pin "1") (pinfunction "1_1") (pintype "passive"))
      (node (ref "C8") (pin "2") (pinfunction "2_2") (pintype "passive"))
      (node (ref "C9") (pin "2") (pinfunction "2_2") (pintype "passive"))
      (node (ref "E1") (pin "GND") (pinfunction "GND_GND") (pintype "bidirectional"))
      (node (ref "E1") (pin "GND2") (pinfunction "GND_GND2") (pintype "bidirectional"))
      (node (ref "IC1") (pin "2") (pinfunction "GND1_2") (pintype "bidirectional"))
      (node (ref "IC1") (pin "6") (pinfunction "PFM/PWM_6") (pintype "bidirectional"))
      (node (ref "IC1") (pin "9") (pinfunction "GND2_9") (pintype "bidirectional"))
      (node (ref "L4") (pin "3-GND") (pinfunction "GND_3-GND") (pintype "bidirectional"))
      (node (ref "MS1") (pin "GND") (pinfunction "GND_GND") (pintype "bidirectional"))
      (node (ref "R13") (pin "2") (pinfunction "2_2") (pintype "passive"))
      (node (ref "R14") (pin "2") (pinfunction "2_2") (pintype "passive"))
      (node (ref "R15") (pin "1") (pinfunction "1_1") (pintype "passive"))
      (node (ref "R16") (pin "1") (pinfunction "1_1") (pintype "passive"))
      (node (ref "R21") (pin "2") (pinfunction "2_2") (pintype "passive"))
      (node (ref "R24") (pin "1") (pinfunction "1_1") (pintype "passive"))
      (node (ref "R26") (pin "1") (pinfunction "1_1") (pintype "passive"))
      (node (ref "R27") (pin "1") (pinfunction "1_1") (pintype "passive"))
      (node (ref "T1") (pin "2") (pinfunction "E_2") (pintype "passive"))
      (node (ref "T2") (pin "2") (pinfunction "E_2") (pintype "passive"))
      (node (ref "U$1") (pin "P$5") (pinfunction "S_P$5") (pintype "passive"))
      (node (ref "U$14") (pin "P$1") (pinfunction "GND_P$1") (pintype "bidirectional"))
      (node (ref "U$16") (pin "10") (pinfunction "VSSA_10") (pintype "bidirectional"))
      (node (ref "U$16") (pin "9") (pinfunction "VSS_9") (pintype "bidirectional"))
      (node (ref "U$2") (pin "VSS") (pinfunction "VSS_VSS") (pintype "bidirectional"))
      (node (ref "U$3") (pin "5") (pinfunction "GND_5") (pintype "bidirectional"))
      (node (ref "U$3") (pin "GND1") (pinfunction "GND_GND1") (pintype "bidirectional"))
      (node (ref "U$3") (pin "GND2") (pinfunction "GND_GND2") (pintype "bidirectional"))
      (node (ref "U$3") (pin "GND3") (pinfunction "GND_GND3") (pintype "bidirectional"))
      (node (ref "U$3") (pin "GND4") (pinfunction "GND_GND4") (pintype "bidirectional"))
      (node (ref "U$4") (pin "P$3") (pinfunction "GND_P$3") (pintype "bidirectional"))
      (node (ref "U$4") (pin "P$4") (pinfunction "GND_P$4") (pintype "bidirectional"))
      (node (ref "U$4") (pin "P$6") (pinfunction "GND_P$6") (pintype "bidirectional"))
      (node (ref "U$5") (pin "P$1") (pinfunction "GND1_P$1") (pintype "bidirectional"))
      (node (ref "U$5") (pin "P$16") (pinfunction "GND6_P$16") (pintype "bidirectional"))
      (node (ref "U$5") (pin "P$2") (pinfunction "GND2_P$2") (pintype "bidirectional"))
      (node (ref "U$5") (pin "P$4") (pinfunction "GND3_P$4") (pintype "bidirectional"))
      (node (ref "U$5") (pin "P$5") (pinfunction "GND4_P$5") (pintype "bidirectional"))
      (node (ref "U$6") (pin "GND") (pinfunction "GND_GND") (pintype "bidirectional"))
      (node (ref "U$7") (pin "GND") (pinfunction "GND_GND") (pintype "bidirectional"))
      (node (ref "U$8") (pin "1") (pinfunction "1_1") (pintype "bidirectional"))
      (node (ref "U1") (pin "10") (pinfunction "SA1/CS_B_10") (pintype "input"))
      (node (ref "U1") (pin "12") (pinfunction "GND_12") (pintype "passive"))
      (node (ref "U1") (pin "13") (pinfunction "RESERVED_13") (pintype "passive"))
      (node (ref "U1") (pin "3") (pinfunction "RESERVED_2_3") (pintype "passive"))
      (node (ref "U1") (pin "5") (pinfunction "GND_2_5") (pintype "passive"))
      (node (ref "U1") (pin "7") (pinfunction "SA0/MISO_7") (pintype "bidirectional"))
      (node (ref "U2") (pin "2") (pinfunction "VSS_2") (pintype "power_in"))
      (node (ref "U4") (pin "B7") (pinfunction "VSS_B7") (pintype "bidirectional"))
      (node (ref "U4") (pin "PAD") (pinfunction "VSS_PAD_PAD") (pintype "bidirectional"))
    )
    (net (code "12") (name "GPS_RST") (class "Default")
      (node (ref "C41") (pin "1") (pinfunction "1_1") (pintype "passive"))
      (node (ref "U$5") (pin "P$7") (pinfunction "HW_R_P$7") (pintype "bidirectional"))
      (node (ref "U4") (pin "J1") (pinfunction "P4_J1") (pintype "bidirectional"))
    )
    (net (code "13") (name "GPS_RX") (class "Default")
      (node (ref "U$5") (pin "P$9") (pinfunction "RX_P$9") (pintype "bidirectional"))
      (node (ref "U4") (pin "R1") (pinfunction "P1.09_R1") (pintype "bidirectional"))
    )
    (net (code "14") (name "GPS_STDBY") (class "Default")
      (node (ref "C40") (pin "1") (pinfunction "1_1") (pintype "passive"))
      (node (ref "U$5") (pin "P$8") (pinfunction "HW_S_P$8") (pintype "bidirectional"))
      (node (ref "U4") (pin "L1") (pinfunction "P6_L1") (pintype "bidirectional"))
    )
    (net (code "15") (name "GPS_TX") (class "Default")
      (node (ref "U$5") (pin "P$10") (pinfunction "TX_P$10") (pintype "bidirectional"))
      (node (ref "U4") (pin "U1") (pinfunction "P12_U1") (pintype "bidirectional"))
    )
    (net (code "16") (name "INT1") (class "Default")
      (node (ref "U1") (pin "11") (pinfunction "INT1_11") (pintype "input"))
      (node (ref "U4") (pin "A10") (pinfunction "P29_A10") (pintype "bidirectional"))
    )
    (net (code "17") (name "INT2") (class "Default")
      (node (ref "U1") (pin "9") (pinfunction "INT2_9") (pintype "input"))
    )
    (net (code "18") (name "INT_PSWITCH") (class "Default")
      (node (ref "D1") (pin "2") (pinfunction "A2_2") (pintype "passive"))
      (node (ref "R10") (pin "2") (pinfunction "2_2") (pintype "passive"))
      (node (ref "R11") (pin "1") (pinfunction "1_1") (pintype "passive"))
      (node (ref "T2") (pin "3") (pinfunction "C_3") (pintype "passive"))
    )
    (net (code "19") (name "KILL_NRF") (class "Default")
      (node (ref "R25") (pin "2") (pinfunction "2_2") (pintype "passive"))
      (node (ref "R26") (pin "2") (pinfunction "2_2") (pintype "passive"))
      (node (ref "U4") (pin "A20") (pinfunction "P1.10_A20") (pintype "bidirectional"))
    )
    (net (code "20") (name "LED_BCK") (class "Default")
      (node (ref "R23") (pin "2") (pinfunction "2_2") (pintype "passive"))
      (node (ref "T1") (pin "1") (pinfunction "B_1") (pintype "passive"))
    )
    (net (code "21") (name "LS027_CS") (class "Default")
      (node (ref "U$16") (pin "3") (pinfunction "CS_3") (pintype "bidirectional"))
      (node (ref "U4") (pin "AD20") (pinfunction "P24_AD20") (pintype "bidirectional"))
    )
    (net (code "22") (name "LS027_MO") (class "Default")
      (node (ref "U$16") (pin "2") (pinfunction "MOSI_2") (pintype "bidirectional"))
      (node (ref "U4") (pin "AD18") (pinfunction "P22_AD18") (pintype "bidirectional"))
    )
    (net (code "23") (name "LS027_SCK") (class "Default")
      (node (ref "U$16") (pin "1") (pinfunction "SCLK_1") (pintype "bidirectional"))
      (node (ref "U4") (pin "AD16") (pinfunction "P20_AD16") (pintype "bidirectional"))
    )
    (net (code "24") (name "MBAT") (class "Default")
      (node (ref "BATT") (pin "1") (pinfunction "1_1") (pintype "passive"))
      (node (ref "R15") (pin "2") (pinfunction "2_2") (pintype "passive"))
      (node (ref "U$6") (pin "CG") (pinfunction "CG_CG") (pintype "bidirectional"))
    )
    (net (code "25") (name "NEO_DIN") (class "Default")
      (node (ref "L4") (pin "4-DIN") (pinfunction "DIN_4-DIN") (pintype "input"))
      (node (ref "Q2") (pin "3") (pinfunction "D_3") (pintype "bidirectional"))
      (node (ref "R18") (pin "1") (pinfunction "1_1") (pintype "passive"))
    )
    (net (code "26") (name "NEO_PIN") (class "Default")
      (node (ref "Q2") (pin "2") (pinfunction "S_2") (pintype "bidirectional"))
      (node (ref "R19") (pin "1") (pinfunction "1_1") (pintype "passive"))
      (node (ref "U4") (pin "G1") (pinfunction "P26_G1") (pintype "bidirectional"))
    )
    (net (code "27") (name "NRF_BTNC") (class "Default")
      (node (ref "C5") (pin "2") (pinfunction "2_2") (pintype "passive"))
      (node (ref "D1") (pin "1") (pinfunction "A1_1") (pintype "passive"))
      (node (ref "R9") (pin "1") (pinfunction "1_1") (pintype "passive"))
      (node (ref "U4") (pin "AD10") (pinfunction "P15_AD10") (pintype "bidirectional"))
    )
    (net (code "28") (name "Net-(E1-SIGNAL)") (class "Default")
      (node (ref "C34") (pin "1") (pinfunction "1_1") (pintype "passive"))
      (node (ref "E1") (pin "ANT") (pinfunction "SIGNAL_ANT") (pintype "bidirectional"))
      (node (ref "FB1") (pin "2") (pinfunction "2_2") (pintype "passive"))
    )
    (net (code "29") (name "Net-(IC1-L1)") (class "Default")
      (node (ref "IC1") (pin "1") (pinfunction "L1_1") (pintype "bidirectional"))
      (node (ref "L1") (pin "1") (pinfunction "1_1") (pintype "bidirectional"))
    )
    (net (code "30") (name "Net-(IC1-L2)") (class "Default")
      (node (ref "IC1") (pin "3") (pinfunction "L2_3") (pintype "bidirectional"))
      (node (ref "L1") (pin "2") (pinfunction "2_2") (pintype "bidirectional"))
    )
    (net (code "31") (name "Net-(IC1-PG)") (class "Default")
      (node (ref "IC1") (pin "8") (pinfunction "PG_8") (pintype "bidirectional"))
      (node (ref "R12") (pin "2") (pinfunction "2_2") (pintype "passive"))
    )
    (net (code "32") (name "Net-(IC1-SS)") (class "Default")
      (node (ref "C13") (pin "2") (pinfunction "2_2") (pintype "passive"))
      (node (ref "IC1") (pin "7") (pinfunction "SS_7") (pintype "bidirectional"))
    )
    (net (code "33") (name "Net-(R20-Pad1)") (class "Default")
      (node (ref "R20") (pin "1") (pinfunction "1_1") (pintype "passive"))
      (node (ref "U$17") (pin "P$1") (pinfunction "P$1_P$1") (pintype "bidirectional"))
      (node (ref "U$18") (pin "P$1") (pinfunction "P$1_P$1") (pintype "bidirectional"))
    )
    (net (code "34") (name "Net-(R21-Pad1)") (class "Default")
      (node (ref "R21") (pin "1") (pinfunction "1_1") (pintype "passive"))
      (node (ref "U$6") (pin "ROSC") (pinfunction "ROSC_ROSC") (pintype "bidirectional"))
    )
    (net (code "35") (name "Net-(R22-Pad2)") (class "Default")
      (node (ref "R22") (pin "2") (pinfunction "2_2") (pintype "passive"))
      (node (ref "U$19") (pin "P$2") (pinfunction "P$2_P$2") (pintype "bidirectional"))
    )
    (net (code "36") (name "Net-(T2-B)") (class "Default")
      (node (ref "R25") (pin "1") (pinfunction "1_1") (pintype "passive"))
      (node (ref "T2") (pin "1") (pinfunction "B_1") (pintype "passive"))
    )
    (net (code "37") (name "Net-(U$1A-D)") (class "Default")
      (node (ref "C1") (pin "1") (pinfunction "1_1") (pintype "passive"))
      (node (ref "C3") (pin "1") (pinfunction "1_1") (pintype "passive"))
      (node (ref "R8") (pin "1") (pinfunction "1_1") (pintype "passive"))
      (node (ref "U$1") (pin "P$3") (pinfunction "G_P$3") (pintype "passive"))
      (node (ref "U$1") (pin "P$6") (pinfunction "D_P$6") (pintype "passive"))
    )
    (net (code "38") (name "Net-(U$1A-G)") (class "Default")
      (node (ref "C4") (pin "1") (pinfunction "1_1") (pintype "passive"))
      (node (ref "R11") (pin "2") (pinfunction "2_2") (pintype "passive"))
      (node (ref "U$1") (pin "P$1") (pinfunction "G_P$1") (pintype "passive"))
    )
    (net (code "39") (name "Net-(U$16-DISP)") (class "Default")
      (node (ref "C43") (pin "2") (pinfunction "2_2") (pintype "passive"))
      (node (ref "R17") (pin "2") (pinfunction "2_2") (pintype "passive"))
      (node (ref "U$16") (pin "5") (pinfunction "DISP_5") (pintype "bidirectional"))
    )
    (net (code "40") (name "Net-(U$16-EXTCOMM)") (class "Default")
      (node (ref "R16") (pin "2") (pinfunction "2_2") (pintype "passive"))
      (node (ref "U$16") (pin "4") (pinfunction "EXTCOMM_4") (pintype "bidirectional"))
    )
    (net (code "41") (name "Net-(U$16-EXTMODE)") (class "Default")
      (node (ref "R13") (pin "1") (pinfunction "1_1") (pintype "passive"))
      (node (ref "U$16") (pin "8") (pinfunction "EXTMODE_8") (pintype "bidirectional"))
    )
    (net (code "42") (name "Net-(U1-BYP)") (class "Default")
      (node (ref "C6") (pin "1") (pinfunction "1_1") (pintype "passive"))
      (node (ref "U1") (pin "2") (pinfunction "BYP_2") (pintype "passive"))
    )
    (net (code "43") (name "Net-(U1-CRST)") (class "Default")
      (node (ref "C7") (pin "2") (pinfunction "2_2") (pintype "passive"))
      (node (ref "U1") (pin "8") (pinfunction "CRST_8") (pintype "passive"))
    )
    (net (code "44") (name "Net-(U2-PROG)") (class "Default")
      (node (ref "R27") (pin "2") (pinfunction "2_2") (pintype "passive"))
      (node (ref "U2") (pin "5") (pinfunction "PROG_5") (pintype "input"))
    )
    (net (code "45") (name "Net-(U4-ANT)") (class "Default")
      (node (ref "C35") (pin "1") (pinfunction "1_1") (pintype "passive"))
      (node (ref "FB1") (pin "1") (pinfunction "1_1") (pintype "passive"))
      (node (ref "U4") (pin "H23") (pinfunction "ANT_H23") (pintype "bidirectional"))
    )
    (net (code "46") (name "Net-(U4-DEC1)") (class "Default")
      (node (ref "C2") (pin "1") (pinfunction "1_1") (pintype "passive"))
      (node (ref "U4") (pin "C1") (pinfunction "DEC1_C1") (pintype "bidirectional"))
    )
    (net (code "47") (name "Net-(U4-DEC2)") (class "Default")
      (node (ref "C25") (pin "2") (pinfunction "2_2") (pintype "passive"))
      (node (ref "U4") (pin "A18") (pinfunction "DEC2_A18") (pintype "bidirectional"))
    )
    (net (code "48") (name "Net-(U4-DEC3)") (class "Default")
      (node (ref "C24") (pin "2") (pinfunction "2_2") (pintype "passive"))
      (node (ref "U4") (pin "D23") (pinfunction "DEC3_D23") (pintype "bidirectional"))
    )
    (net (code "49") (name "Net-(U4-DEC5)") (class "Default")
      (node (ref "C29") (pin "2") (pinfunction "2_2") (pintype "passive"))
      (node (ref "U4") (pin "N24") (pinfunction "DEC5_N24") (pintype "bidirectional"))
    )
    (net (code "50") (name "Net-(U4-VSS_PA)") (class "Default")
      (node (ref "C35") (pin "2") (pinfunction "2_2") (pintype "passive"))
      (node (ref "U$8") (pin "2") (pinfunction "2_2") (pintype "bidirectional"))
      (node (ref "U4") (pin "F23") (pinfunction "VSS_PA_F23") (pintype "bidirectional"))
    )
    (net (code "51") (name "PIN_BCK") (class "Default")
      (node (ref "R23") (pin "1") (pinfunction "1_1") (pintype "passive"))
      (node (ref "R24") (pin "2") (pinfunction "2_2") (pintype "passive"))
    )
    (net (code "52") (name "PPS") (class "Default")
      (node (ref "U$5") (pin "P$6") (pinfunction "PPS_P$6") (pintype "bidirectional"))
    )
    (net (code "53") (name "PW_EN") (class "Default")
      (node (ref "C4") (pin "2") (pinfunction "2_2") (pintype "passive"))
      (node (ref "IC1") (pin "11") (pinfunction "EN_11") (pintype "bidirectional"))
      (node (ref "L4") (pin "1-VDD") (pinfunction "VDD_1-VDD") (pintype "bidirectional"))
      (node (ref "R10") (pin "1") (pinfunction "1_1") (pintype "passive"))
      (node (ref "R14") (pin "1") (pinfunction "1_1") (pintype "passive"))
      (node (ref "R18") (pin "2") (pinfunction "2_2") (pintype "passive"))
      (node (ref "U$1") (pin "P$4") (pinfunction "D_P$4") (pintype "passive"))
    )
    (net (code "54") (name "RF_IN") (class "Default")
      (node (ref "C38") (pin "1") (pinfunction "1_1") (pintype "passive"))
      (node (ref "L2") (pin "2") (pinfunction "2_2") (pintype "passive"))
      (node (ref "U$5") (pin "P$3") (pinfunction "RF_IN_P$3") (pintype "bidirectional"))
    )
    (net (code "55") (name "SCL") (class "Default")
      (node (ref "MS1") (pin "SCL") (pinfunction "SCL_SCL") (pintype "bidirectional"))
      (node (ref "R31") (pin "2") (pinfunction "2_2") (pintype "passive"))
      (node (ref "U$14") (pin "P$3") (pinfunction "SCL_P$3") (pintype "bidirectional"))
      (node (ref "U$6") (pin "SCL") (pinfunction "SCL_SCL") (pintype "bidirectional"))
      (node (ref "U1") (pin "4") (pinfunction "SCL/SCLK_4") (pintype "input"))
      (node (ref "U4") (pin "A16") (pinfunction "P1.13_A16") (pintype "bidirectional"))
    )
    (net (code "56") (name "SDA") (class "Default")
      (node (ref "MS1") (pin "SDA") (pinfunction "SDA_SDA") (pintype "bidirectional"))
      (node (ref "R30") (pin "2") (pinfunction "2_2") (pintype "passive"))
      (node (ref "U$14") (pin "P$2") (pinfunction "SDA_P$2") (pintype "bidirectional"))
      (node (ref "U$6") (pin "SDA") (pinfunction "SDA_SDA") (pintype "bidirectional"))
      (node (ref "U1") (pin "6") (pinfunction "SDA/MOSI_6") (pintype "bidirectional"))
      (node (ref "U4") (pin "A14") (pinfunction "P1.15_A14") (pintype "bidirectional"))
    )
    (net (code "57") (name "SPI_MI") (class "Default")
      (node (ref "U$2") (pin "SO") (pinfunction "SO_SO") (pintype "bidirectional"))
      (node (ref "U4") (pin "J24") (pinfunction "P10_J24") (pintype "bidirectional"))
    )
    (net (code "58") (name "SPI_MO") (class "Default")
      (node (ref "U$2") (pin "SI") (pinfunction "SI_SI") (pintype "bidirectional"))
      (node (ref "U4") (pin "W24") (pinfunction "P1.02_W24") (pintype "bidirectional"))
    )
    (net (code "59") (name "SPI_SCK") (class "Default")
      (node (ref "U$2") (pin "SCK") (pinfunction "SCK_SCK") (pintype "bidirectional"))
      (node (ref "U4") (pin "U24") (pinfunction "P1.04_U24") (pintype "bidirectional"))
    )
    (net (code "60") (name "SST_CS") (class "Default")
      (node (ref "U$2") (pin "CE") (pinfunction "CE_CE") (pintype "bidirectional"))
      (node (ref "U4") (pin "R24") (pinfunction "P1.06_R24") (pintype "bidirectional"))
    )
    (net (code "61") (name "SST_HOLD") (class "Default")
      (node (ref "U$2") (pin "HOLD") (pinfunction "HOLD_HOLD") (pintype "bidirectional"))
      (node (ref "U4") (pin "AD22") (pinfunction "P1.00_AD22") (pintype "bidirectional"))
    )
    (net (code "62") (name "SST_WP") (class "Default")
      (node (ref "U$2") (pin "WP") (pinfunction "WP_WP") (pintype "bidirectional"))
      (node (ref "U4") (pin "L24") (pinfunction "P9_L24") (pintype "bidirectional"))
    )
    (net (code "63") (name "SWDCLK") (class "Default")
      (node (ref "U$7") (pin "PIN1") (pinfunction "SWDCLK_PIN1") (pintype "bidirectional"))
      (node (ref "U4") (pin "AA24") (pinfunction "SWDCLK_AA24") (pintype "bidirectional"))
    )
    (net (code "64") (name "SWDIO") (class "Default")
      (node (ref "U$7") (pin "PIN2") (pinfunction "SWDIO_PIN2") (pintype "bidirectional"))
      (node (ref "U4") (pin "AC24") (pinfunction "SWDIO_AC24") (pintype "bidirectional"))
    )
    (net (code "65") (name "USB_D0_N") (class "Default")
      (node (ref "R2") (pin "2") (pinfunction "2_2") (pintype "passive"))
      (node (ref "U4") (pin "AD4") (pinfunction "D-_AD4") (pintype "bidirectional"))
    )
    (net (code "66") (name "USB_D0_P") (class "Default")
      (node (ref "R1") (pin "2") (pinfunction "2_2") (pintype "passive"))
      (node (ref "U4") (pin "AD6") (pinfunction "D+_AD6") (pintype "bidirectional"))
    )
    (net (code "67") (name "USB_D1_N") (class "Default")
      (node (ref "R2") (pin "1") (pinfunction "1_1") (pintype "passive"))
      (node (ref "U$3") (pin "2") (pinfunction "DM_2") (pintype "bidirectional"))
    )
    (net (code "68") (name "USB_D1_P") (class "Default")
      (node (ref "R1") (pin "1") (pinfunction "1_1") (pintype "passive"))
      (node (ref "U$3") (pin "3") (pinfunction "DP_3") (pintype "bidirectional"))
    )
    (net (code "69") (name "VBAT") (class "Default")
      (node (ref "BATT") (pin "2") (pinfunction "2_2") (pintype "passive"))
      (node (ref "C14") (pin "1") (pinfunction "1_1") (pintype "passive"))
      (node (ref "C16") (pin "2") (pinfunction "2_2") (pintype "passive"))
      (node (ref "D3") (pin "2") (pinfunction "A2_2") (pintype "passive"))
      (node (ref "R3") (pin "2") (pinfunction "2_2") (pintype "passive"))
      (node (ref "R8") (pin "2") (pinfunction "2_2") (pintype "passive"))
      (node (ref "U$1") (pin "P$2") (pinfunction "S_P$2") (pintype "passive"))
      (node (ref "U$5") (pin "P$14") (pinfunction "BV_P$14") (pintype "bidirectional"))
      (node (ref "U$6") (pin "VCC") (pinfunction "VCC_VCC") (pintype "bidirectional"))
      (node (ref "U$6") (pin "VIN") (pinfunction "VIN_VIN") (pintype "bidirectional"))
      (node (ref "U2") (pin "3") (pinfunction "VBAT_3") (pintype "power_in"))
    )
    (net (code "70") (name "VCC") (class "Default")
      (node (ref "C10") (pin "1") (pinfunction "1_1") (pintype "passive"))
      (node (ref "C12") (pin "2") (pinfunction "2_2") (pintype "passive"))
      (node (ref "C17") (pin "1") (pinfunction "1_1") (pintype "passive"))
      (node (ref "C18") (pin "1") (pinfunction "1_1") (pintype "passive"))
      (node (ref "C22") (pin "2") (pinfunction "2_2") (pintype "passive"))
      (node (ref "C26") (pin "1") (pinfunction "1_1") (pintype "passive"))
      (node (ref "C30") (pin "1") (pinfunction "1_1") (pintype "passive"))
      (node (ref "C31") (pin "1") (pinfunction "1_1") (pintype "passive"))
      (node (ref "C36") (pin "2") (pinfunction "2_2") (pintype "passive"))
      (node (ref "C37") (pin "2") (pinfunction "2_2") (pintype "passive"))
      (node (ref "C44") (pin "2") (pinfunction "2_2") (pintype "passive"))
      (node (ref "C8") (pin "1") (pinfunction "1_1") (pintype "passive"))
      (node (ref "C9") (pin "1") (pinfunction "1_1") (pintype "passive"))
      (node (ref "IC1") (pin "4") (pinfunction "VOUT_4") (pintype "bidirectional"))
      (node (ref "IC1") (pin "5") (pinfunction "FB_5") (pintype "bidirectional"))
      (node (ref "MS1") (pin "VDD") (pinfunction "VDD_VDD") (pintype "bidirectional"))
      (node (ref "Q2") (pin "1") (pinfunction "G_1") (pintype "bidirectional"))
      (node (ref "R12") (pin "1") (pinfunction "1_1") (pintype "passive"))
      (node (ref "R17") (pin "1") (pinfunction "1_1") (pintype "passive"))
      (node (ref "R19") (pin "2") (pinfunction "2_2") (pintype "passive"))
      (node (ref "R22") (pin "1") (pinfunction "1_1") (pintype "passive"))
      (node (ref "R30") (pin "1") (pinfunction "1_1") (pintype "passive"))
      (node (ref "R31") (pin "1") (pinfunction "1_1") (pintype "passive"))
      (node (ref "R9") (pin "2") (pinfunction "2_2") (pintype "passive"))
      (node (ref "U$14") (pin "P$4") (pinfunction "VDD_P$4") (pintype "bidirectional"))
      (node (ref "U$16") (pin "6") (pinfunction "VDDA_6") (pintype "bidirectional"))
      (node (ref "U$16") (pin "7") (pinfunction "VDD_7") (pintype "bidirectional"))
      (node (ref "U$17") (pin "P$2") (pinfunction "P$2_P$2") (pintype "bidirectional"))
      (node (ref "U$18") (pin "P$2") (pinfunction "P$2_P$2") (pintype "bidirectional"))
      (node (ref "U$2") (pin "VDD") (pinfunction "VDD_VDD") (pintype "bidirectional"))
      (node (ref "U$5") (pin "P$15") (pinfunction "VCC_P$15") (pintype "bidirectional"))
      (node (ref "U$7") (pin "VCC") (pinfunction "VCC_VCC") (pintype "bidirectional"))
      (node (ref "U1") (pin "1") (pinfunction "VDDIO_1") (pintype "power_in"))
      (node (ref "U1") (pin "14") (pinfunction "VDD_14") (pintype "power_in"))
      (node (ref "U4") (pin "A22") (pinfunction "VDD2_A22") (pintype "bidirectional"))
      (node (ref "U4") (pin "AD14") (pinfunction "VDD4_AD14") (pintype "bidirectional"))
      (node (ref "U4") (pin "AD23") (pinfunction "VDD3_AD23") (pintype "bidirectional"))
      (node (ref "U4") (pin "B1") (pinfunction "VDD1_B1") (pintype "bidirectional"))
      (node (ref "U4") (pin "W1") (pinfunction "VDD6_W1") (pintype "bidirectional"))
      (node (ref "U4") (pin "Y2") (pinfunction "VDDH_Y2") (pintype "bidirectional"))
    )
    (net (code "71") (name "VIN") (class "Default")
      (node (ref "C11") (pin "2") (pinfunction "2_2") (pintype "passive"))
      (node (ref "D3") (pin "3") (pinfunction "CC_3") (pintype "passive"))
      (node (ref "IC1") (pin "10") (pinfunction "ILIM0_10") (pintype "bidirectional"))
      (node (ref "IC1") (pin "12") (pinfunction "VIN_12") (pintype "bidirectional"))
    )
    (net (code "72") (name "VUSB") (class "Default")
      (node (ref "C15") (pin "2") (pinfunction "2_2") (pintype "passive"))
      (node (ref "C19") (pin "1") (pinfunction "1_1") (pintype "passive"))
      (node (ref "C21") (pin "1") (pinfunction "1_1") (pintype "passive"))
      (node (ref "D3") (pin "1") (pinfunction "A1_1") (pintype "passive"))
      (node (ref "U$3") (pin "1") (pinfunction "VCC_1") (pintype "bidirectional"))
      (node (ref "U2") (pin "4") (pinfunction "VIN_4") (pintype "power_in"))
      (node (ref "U4") (pin "AD2") (pinfunction "VBUS_AD2") (pintype "bidirectional"))
    )
    (net (code "73") (name "XC1") (class "Default")
      (node (ref "C28") (pin "2") (pinfunction "2_2") (pintype "passive"))
      (node (ref "U4") (pin "B24") (pinfunction "XC1_B24") (pintype "bidirectional"))
      (node (ref "Y2") (pin "1") (pinfunction "1_1") (pintype "passive"))
    )
    (net (code "74") (name "XC2") (class "Default")
      (node (ref "C27") (pin "2") (pinfunction "2_2") (pintype "passive"))
      (node (ref "U4") (pin "A23") (pinfunction "XC2_A23") (pintype "bidirectional"))
      (node (ref "Y2") (pin "3") (pinfunction "2_3") (pintype "passive"))
    )
    (net (code "75") (name "XL1") (class "Default")
      (node (ref "C33") (pin "2") (pinfunction "2_2") (pintype "passive"))
      (node (ref "U4") (pin "D2") (pinfunction "P0/XL1_D2") (pintype "bidirectional"))
      (node (ref "Y3") (pin "P$1") (pinfunction "1_P$1") (pintype "passive"))
    )
    (net (code "76") (name "XL2") (class "Default")
      (node (ref "C32") (pin "2") (pinfunction "2_2") (pintype "passive"))
      (node (ref "U4") (pin "F2") (pinfunction "P1/XL2_F2") (pintype "bidirectional"))
      (node (ref "Y3") (pin "P$2") (pinfunction "2_P$2") (pintype "passive"))
    )
    (net (code "77") (name "unconnected-(L4-DOUT-Pad2-DOUT)") (class "Default")
      (node (ref "L4") (pin "2-DOUT") (pinfunction "DOUT_2-DOUT") (pintype "output"))
    )
    (net (code "78") (name "unconnected-(U$3-SNS-Pad4)") (class "Default")
      (node (ref "U$3") (pin "4") (pinfunction "SNS_4") (pintype "bidirectional"))
    )
    (net (code "79") (name "unconnected-(U$5-E2-PadP$11)") (class "Default")
      (node (ref "U$5") (pin "P$11") (pinfunction "E2_P$11") (pintype "bidirectional"))
    )
    (net (code "80") (name "unconnected-(U$5-E3-PadP$12)") (class "Default")
      (node (ref "U$5") (pin "P$12") (pinfunction "E3_P$12") (pintype "bidirectional"))
    )
    (net (code "81") (name "unconnected-(U$6-PadIO)") (class "Default")
      (node (ref "U$6") (pin "IO") (pinfunction "IO_IO") (pintype "bidirectional"))
    )
    (net (code "82") (name "unconnected-(U1-N{slash}C-Pad15)") (class "Default")
      (node (ref "U1") (pin "15") (pinfunction "N/C_15") (pintype "no_connect"))
    )
    (net (code "83") (name "unconnected-(U2-STAT-Pad1)") (class "Default")
      (node (ref "U2") (pin "1") (pinfunction "STAT_1") (pintype "output"))
    )
    (net (code "84") (name "unconnected-(U4-DCC1-PadB3)") (class "Default")
      (node (ref "U4") (pin "B3") (pinfunction "DCC1_B3") (pintype "bidirectional"))
    )
    (net (code "85") (name "unconnected-(U4-DCCH-PadAB2)") (class "Default")
      (node (ref "U4") (pin "AB2") (pinfunction "DCCH_AB2") (pintype "bidirectional"))
    )
    (net (code "86") (name "unconnected-(U4-P1.01-PadY23)") (class "Default")
      (node (ref "U4") (pin "Y23") (pinfunction "P1.01_Y23") (pintype "bidirectional"))
    )
    (net (code "87") (name "unconnected-(U4-P1.03-PadV23)") (class "Default")
      (node (ref "U4") (pin "V23") (pinfunction "P1.03_V23") (pintype "bidirectional"))
    )
    (net (code "88") (name "unconnected-(U4-P1.05-PadT23)") (class "Default")
      (node (ref "U4") (pin "T23") (pinfunction "P1.05_T23") (pintype "bidirectional"))
    )
    (net (code "89") (name "unconnected-(U4-P1.07-PadP23)") (class "Default")
      (node (ref "U4") (pin "P23") (pinfunction "P1.07_P23") (pintype "bidirectional"))
    )
    (net (code "90") (name "unconnected-(U4-P1.08-PadP2)") (class "Default")
      (node (ref "U4") (pin "P2") (pinfunction "P1.08_P2") (pintype "bidirectional"))
    )
    (net (code "91") (name "unconnected-(U4-P1.11-PadB19)") (class "Default")
      (node (ref "U4") (pin "B19") (pinfunction "P1.11_B19") (pintype "bidirectional"))
    )
    (net (code "92") (name "unconnected-(U4-P1.12-PadB17)") (class "Default")
      (node (ref "U4") (pin "B17") (pinfunction "P1.12_B17") (pintype "bidirectional"))
    )
    (net (code "93") (name "unconnected-(U4-P1.14-PadB15)") (class "Default")
      (node (ref "U4") (pin "B15") (pinfunction "P1.14_B15") (pintype "bidirectional"))
    )
    (net (code "94") (name "unconnected-(U4-P3-PadB13)") (class "Default")
      (node (ref "U4") (pin "B13") (pinfunction "P3_B13") (pintype "bidirectional"))
    )
    (net (code "95") (name "unconnected-(U4-P5-PadK2)") (class "Default")
      (node (ref "U4") (pin "K2") (pinfunction "P5_K2") (pintype "bidirectional"))
    )
    (net (code "96") (name "unconnected-(U4-P7-PadM2)") (class "Default")
      (node (ref "U4") (pin "M2") (pinfunction "P7_M2") (pintype "bidirectional"))
    )
    (net (code "97") (name "unconnected-(U4-P11-PadT2)") (class "Default")
      (node (ref "U4") (pin "T2") (pinfunction "P11_T2") (pintype "bidirectional"))
    )
    (net (code "98") (name "unconnected-(U4-P14-PadAC9)") (class "Default")
      (node (ref "U4") (pin "AC9") (pinfunction "P14_AC9") (pintype "bidirectional"))
    )
    (net (code "99") (name "unconnected-(U4-P16-PadAC11)") (class "Default")
      (node (ref "U4") (pin "AC11") (pinfunction "P16_AC11") (pintype "bidirectional"))
    )
    (net (code "100") (name "unconnected-(U4-P18{slash}RST-PadAC13)") (class "Default")
      (node (ref "U4") (pin "AC13") (pinfunction "P18/RST_AC13") (pintype "bidirectional"))
    )
    (net (code "101") (name "unconnected-(U4-P19-PadAC15)") (class "Default")
      (node (ref "U4") (pin "AC15") (pinfunction "P19_AC15") (pintype "bidirectional"))
    )
    (net (code "102") (name "unconnected-(U4-P21-PadAC17)") (class "Default")
      (node (ref "U4") (pin "AC17") (pinfunction "P21_AC17") (pintype "bidirectional"))
    )
    (net (code "103") (name "unconnected-(U4-P23-PadAC19)") (class "Default")
      (node (ref "U4") (pin "AC19") (pinfunction "P23_AC19") (pintype "bidirectional"))
    )
    (net (code "104") (name "unconnected-(U4-P25-PadAC21)") (class "Default")
      (node (ref "U4") (pin "AC21") (pinfunction "P25_AC21") (pintype "bidirectional"))
    )
    (net (code "105") (name "unconnected-(U4-P27-PadH2)") (class "Default")
      (node (ref "U4") (pin "H2") (pinfunction "P27_H2") (pintype "bidirectional"))
    )
    (net (code "106") (name "unconnected-(U4-P28-PadB11)") (class "Default")
      (node (ref "U4") (pin "B11") (pinfunction "P28_B11") (pintype "bidirectional"))
    )
    (net (code "107") (name "unconnected-(U4-P30-PadB9)") (class "Default")
      (node (ref "U4") (pin "B9") (pinfunction "P30_B9") (pintype "bidirectional"))
    )
  )
)
